# SparkFun_VL6180_Sensor.net
KiCad netlist of a schematic drawn in EAGLE
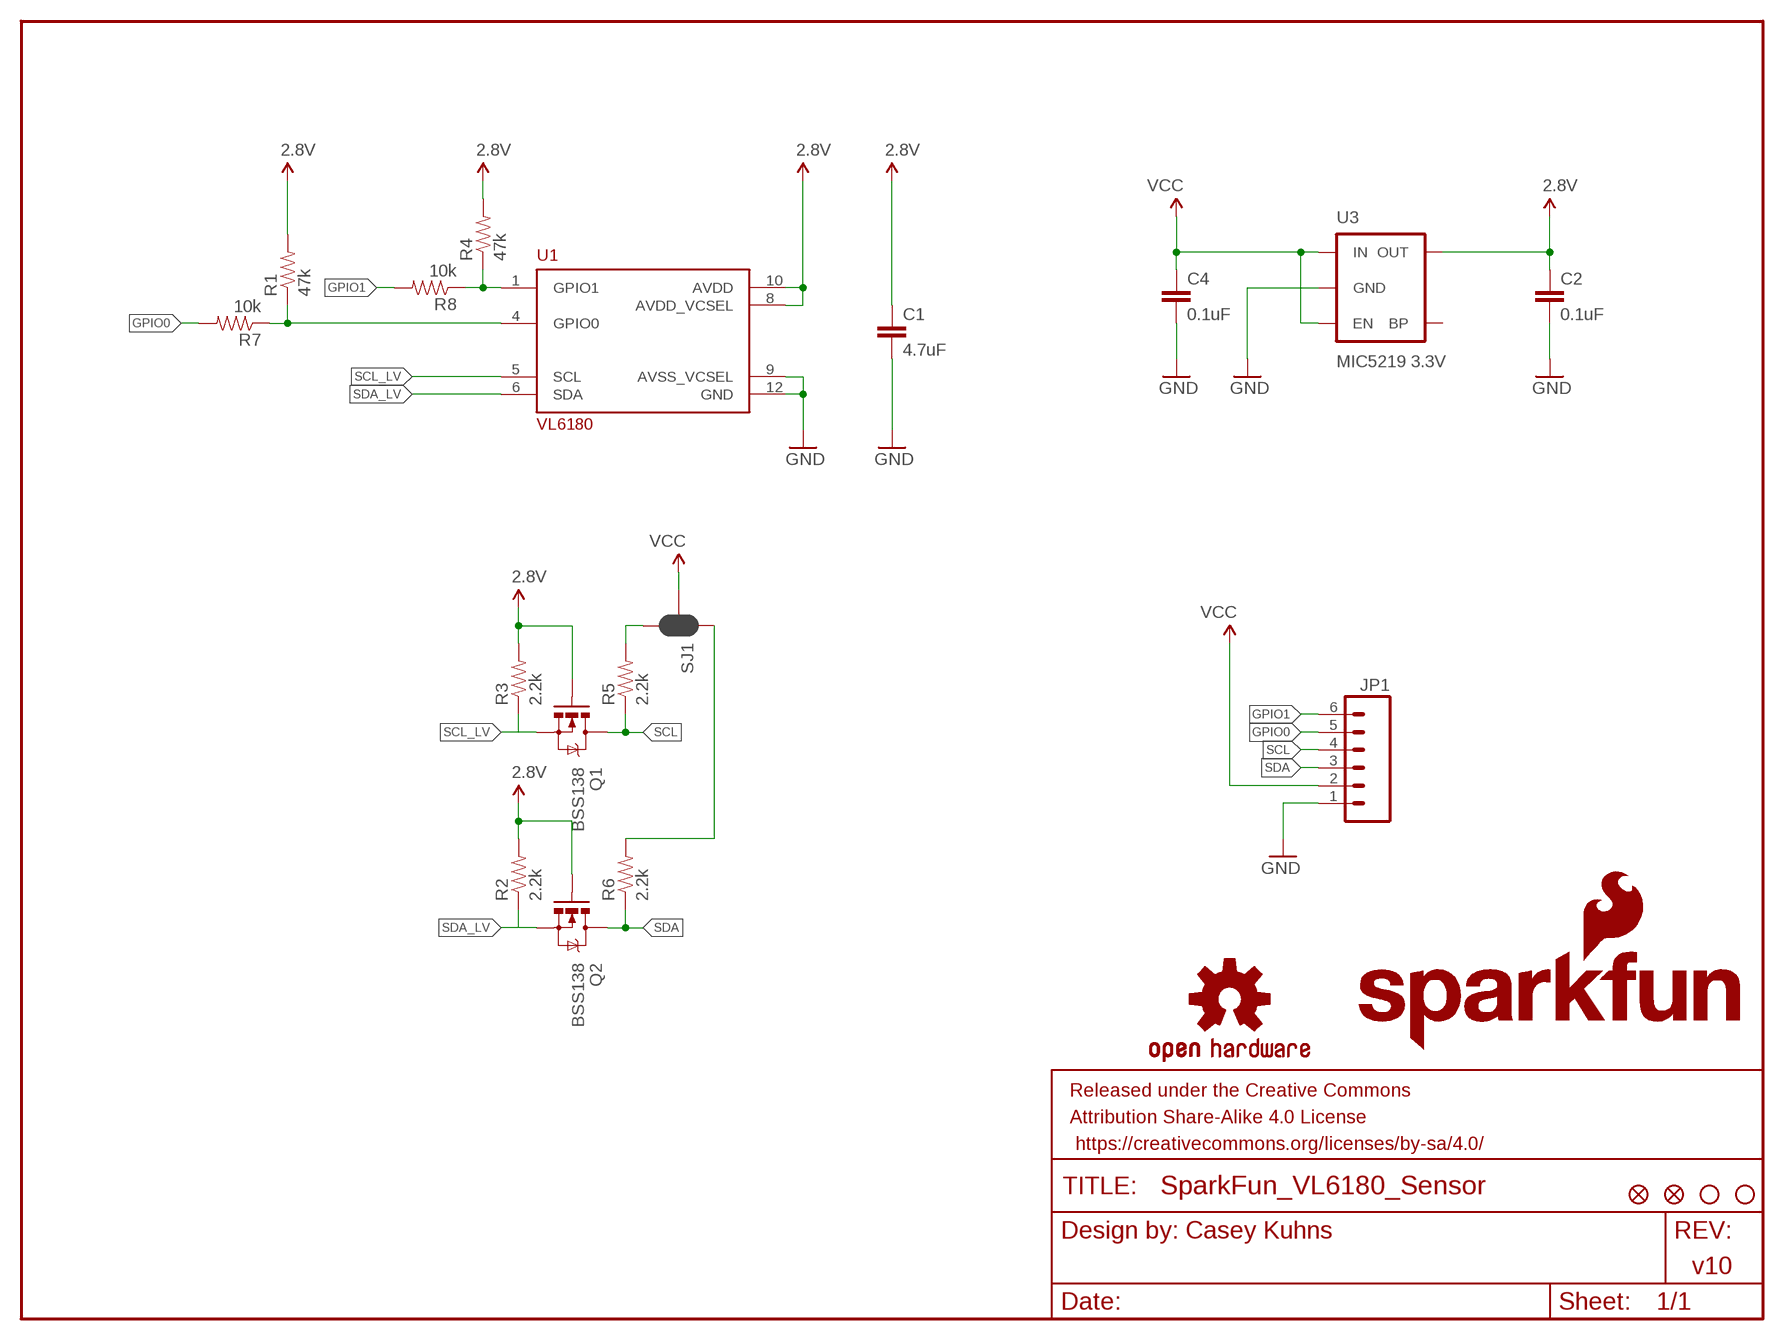
[diagram p0: schematic, sheet 1]

(export (version "E")
  (design (tool "Eeschema 10.0.6"))
  (components
    (comp (ref "C1")
      (value "4.7uF")
      (footprint "eagle-import:0603-CAP")
      (libsource (lib "eagle-import") (part "4.7UF-6.3V-10%(0603)0603"))
    )
    (comp (ref "C2")
      (value "0.1uF")
      (footprint "eagle-import:0603-CAP")
      (libsource (lib "eagle-import") (part "0.1UF-25V(+80/-20%)(0603)"))
    )
    (comp (ref "C4")
      (value "0.1uF")
      (footprint "eagle-import:0603-CAP")
      (libsource (lib "eagle-import") (part "0.1UF-25V(+80/-20%)(0603)"))
    )
    (comp (ref "FID1")
      (value "FIDUCIAL1X2")
      (footprint "eagle-import:FIDUCIAL-1X2")
      (libsource (lib "eagle-import") (part "FIDUCIAL1X2"))
    )
    (comp (ref "FID2")
      (value "FIDUCIAL1X2")
      (footprint "eagle-import:FIDUCIAL-1X2")
      (libsource (lib "eagle-import") (part "FIDUCIAL1X2"))
    )
    (comp (ref "FRAME1")
      (value "FRAME-LETTER")
      (footprint "eagle-import:CREATIVE_COMMONS")
      (libsource (lib "eagle-import") (part "FRAME-LETTER"))
    )
    (comp (ref "JP1")
      (value "M06SIP")
      (footprint "eagle-import:1X06")
      (libsource (lib "eagle-import") (part "M06SIP"))
    )
    (comp (ref "LOGO1")
      (value "SFE_LOGO_NAME_FLAME.1_INCH")
      (footprint "eagle-import:SFE_LOGO_NAME_FLAME_.1")
      (libsource (lib "eagle-import") (part "SFE_LOGO_NAME_FLAME.1_INCH"))
    )
    (comp (ref "LOGO2")
      (value "OSHW-LOGOS")
      (footprint "eagle-import:OSHW-LOGO-S")
      (libsource (lib "eagle-import") (part "OSHW-LOGOS"))
    )
    (comp (ref "Q1")
      (value "BSS138")
      (footprint "eagle-import:SOT23")
      (libsource (lib "eagle-import") (part "MOSFET-NCHANNELBSS138"))
    )
    (comp (ref "Q2")
      (value "BSS138")
      (footprint "eagle-import:SOT23")
      (libsource (lib "eagle-import") (part "MOSFET-NCHANNELBSS138"))
    )
    (comp (ref "R1")
      (value "47k")
      (footprint "eagle-import:0603-RES")
      (libsource (lib "eagle-import") (part "47KOHM1/10W1%(0603)"))
    )
    (comp (ref "R2")
      (value "2.2k")
      (footprint "eagle-import:0603-RES")
      (libsource (lib "eagle-import") (part "2.2KOHM1/10W1%(0603)"))
    )
    (comp (ref "R3")
      (value "2.2k")
      (footprint "eagle-import:0603-RES")
      (libsource (lib "eagle-import") (part "2.2KOHM1/10W1%(0603)"))
    )
    (comp (ref "R4")
      (value "47k")
      (footprint "eagle-import:0603-RES")
      (libsource (lib "eagle-import") (part "47KOHM1/10W1%(0603)"))
    )
    (comp (ref "R5")
      (value "2.2k")
      (footprint "eagle-import:0603-RES")
      (libsource (lib "eagle-import") (part "2.2KOHM1/10W1%(0603)"))
    )
    (comp (ref "R6")
      (value "2.2k")
      (footprint "eagle-import:0603-RES")
      (libsource (lib "eagle-import") (part "2.2KOHM1/10W1%(0603)"))
    )
    (comp (ref "R7")
      (value "10k")
      (footprint "eagle-import:0603-RES")
      (libsource (lib "eagle-import") (part "10KOHM1/10W1%(0603)0603"))
    )
    (comp (ref "R8")
      (value "10k")
      (footprint "eagle-import:0603-RES")
      (libsource (lib "eagle-import") (part "10KOHM1/10W1%(0603)0603"))
    )
    (comp (ref "SJ1")
      (value "JUMPER-PAD-3-NC_BY_PASTE")
      (footprint "eagle-import:PAD-JUMPER-3-NC_BY_PASTE_YES_SILK_FULL_BOX")
      (libsource (lib "eagle-import") (part "JUMPER-PAD-3-NC_BY_PASTE"))
    )
    (comp (ref "STANDOFF1")
      (value "STAND-OFF")
      (footprint "eagle-import:STAND-OFF")
      (libsource (lib "eagle-import") (part "STAND-OFF"))
    )
    (comp (ref "STANDOFF2")
      (value "STAND-OFF")
      (footprint "eagle-import:STAND-OFF")
      (libsource (lib "eagle-import") (part "STAND-OFF"))
    )
    (comp (ref "U1")
      (value "VL6180")
      (footprint "eagle-import:VL6180")
      (libsource (lib "eagle-import") (part "VL6180"))
    )
    (comp (ref "U3")
      (value "MIC5219 3.3V")
      (footprint "eagle-import:SOT23-5")
      (libsource (lib "eagle-import") (part "V_REG_MIC52193.3V"))
    )
  )
  (nets
    (net (code "1") (name "2.8V") (class "Default")
      (node (ref "C1") (pin "1") (pinfunction "1_1") (pintype "passive"))
      (node (ref "C2") (pin "1") (pinfunction "1_1") (pintype "passive"))
      (node (ref "Q1") (pin "1") (pinfunction "G_1") (pintype "passive"))
      (node (ref "Q2") (pin "1") (pinfunction "G_1") (pintype "passive"))
      (node (ref "R1") (pin "2") (pinfunction "2_2") (pintype "passive"))
      (node (ref "R2") (pin "2") (pinfunction "2_2") (pintype "passive"))
      (node (ref "R3") (pin "2") (pinfunction "2_2") (pintype "passive"))
      (node (ref "R4") (pin "2") (pinfunction "2_2") (pintype "passive"))
      (node (ref "U1") (pin "10") (pinfunction "AVDD_10") (pintype "bidirectional"))
      (node (ref "U1") (pin "8") (pinfunction "AVDD_VCSEL_8") (pintype "bidirectional"))
      (node (ref "U3") (pin "5") (pinfunction "OUT_5") (pintype "passive"))
    )
    (net (code "2") (name "GND") (class "Default")
      (node (ref "C1") (pin "2") (pinfunction "2_2") (pintype "passive"))
      (node (ref "C2") (pin "2") (pinfunction "2_2") (pintype "passive"))
      (node (ref "C4") (pin "2") (pinfunction "2_2") (pintype "passive"))
      (node (ref "JP1") (pin "1") (pinfunction "1_1") (pintype "passive"))
      (node (ref "U1") (pin "12") (pinfunction "GND_12") (pintype "bidirectional"))
      (node (ref "U1") (pin "9") (pinfunction "AVSS_VCSEL_9") (pintype "bidirectional"))
      (node (ref "U3") (pin "2") (pinfunction "GND_2") (pintype "input"))
    )
    (net (code "3") (name "GPIO0") (class "Default")
      (node (ref "JP1") (pin "5") (pinfunction "5_5") (pintype "passive"))
      (node (ref "R7") (pin "2") (pinfunction "2_2") (pintype "passive"))
    )
    (net (code "4") (name "GPIO1") (class "Default")
      (node (ref "JP1") (pin "6") (pinfunction "6_6") (pintype "passive"))
      (node (ref "R8") (pin "2") (pinfunction "2_2") (pintype "passive"))
    )
    (net (code "5") (name "Net-(R5-Pad2)") (class "Default")
      (node (ref "R5") (pin "2") (pinfunction "2_2") (pintype "passive"))
      (node (ref "SJ1") (pin "3") (pinfunction "3_3") (pintype "passive"))
    )
    (net (code "6") (name "Net-(R6-Pad2)") (class "Default")
      (node (ref "R6") (pin "2") (pinfunction "2_2") (pintype "passive"))
      (node (ref "SJ1") (pin "1") (pinfunction "1_1") (pintype "passive"))
    )
    (net (code "7") (name "Net-(U1-GPIO0)") (class "Default")
      (node (ref "R1") (pin "1") (pinfunction "1_1") (pintype "passive"))
      (node (ref "R7") (pin "1") (pinfunction "1_1") (pintype "passive"))
      (node (ref "U1") (pin "4") (pinfunction "GPIO0_4") (pintype "bidirectional"))
    )
    (net (code "8") (name "Net-(U1-GPIO1)") (class "Default")
      (node (ref "R4") (pin "1") (pinfunction "1_1") (pintype "passive"))
      (node (ref "R8") (pin "1") (pinfunction "1_1") (pintype "passive"))
      (node (ref "U1") (pin "1") (pinfunction "GPIO1_1") (pintype "bidirectional"))
    )
    (net (code "9") (name "SCL") (class "Default")
      (node (ref "JP1") (pin "4") (pinfunction "4_4") (pintype "passive"))
      (node (ref "Q1") (pin "3") (pinfunction "D_3") (pintype "passive"))
      (node (ref "R5") (pin "1") (pinfunction "1_1") (pintype "passive"))
    )
    (net (code "10") (name "SCL_LV") (class "Default")
      (node (ref "Q1") (pin "2") (pinfunction "S_2") (pintype "passive"))
      (node (ref "R3") (pin "1") (pinfunction "1_1") (pintype "passive"))
      (node (ref "U1") (pin "5") (pinfunction "SCL_5") (pintype "bidirectional"))
    )
    (net (code "11") (name "SDA") (class "Default")
      (node (ref "JP1") (pin "3") (pinfunction "3_3") (pintype "passive"))
      (node (ref "Q2") (pin "3") (pinfunction "D_3") (pintype "passive"))
      (node (ref "R6") (pin "1") (pinfunction "1_1") (pintype "passive"))
    )
    (net (code "12") (name "SDA_LV") (class "Default")
      (node (ref "Q2") (pin "2") (pinfunction "S_2") (pintype "passive"))
      (node (ref "R2") (pin "1") (pinfunction "1_1") (pintype "passive"))
      (node (ref "U1") (pin "6") (pinfunction "SDA_6") (pintype "bidirectional"))
    )
    (net (code "13") (name "VCC") (class "Default")
      (node (ref "C4") (pin "1") (pinfunction "1_1") (pintype "passive"))
      (node (ref "JP1") (pin "2") (pinfunction "2_2") (pintype "passive"))
      (node (ref "SJ1") (pin "2") (pinfunction "2_2") (pintype "passive"))
      (node (ref "U3") (pin "1") (pinfunction "IN_1") (pintype "input"))
      (node (ref "U3") (pin "3") (pinfunction "EN_3") (pintype "input"))
    )
    (net (code "14") (name "unconnected-(U3-BP-Pad4)") (class "Default")
      (node (ref "U3") (pin "4") (pinfunction "BP_4") (pintype "input"))
    )
  )
)
